# untitled.net
KiCad netlist of a schematic drawn in EAGLE
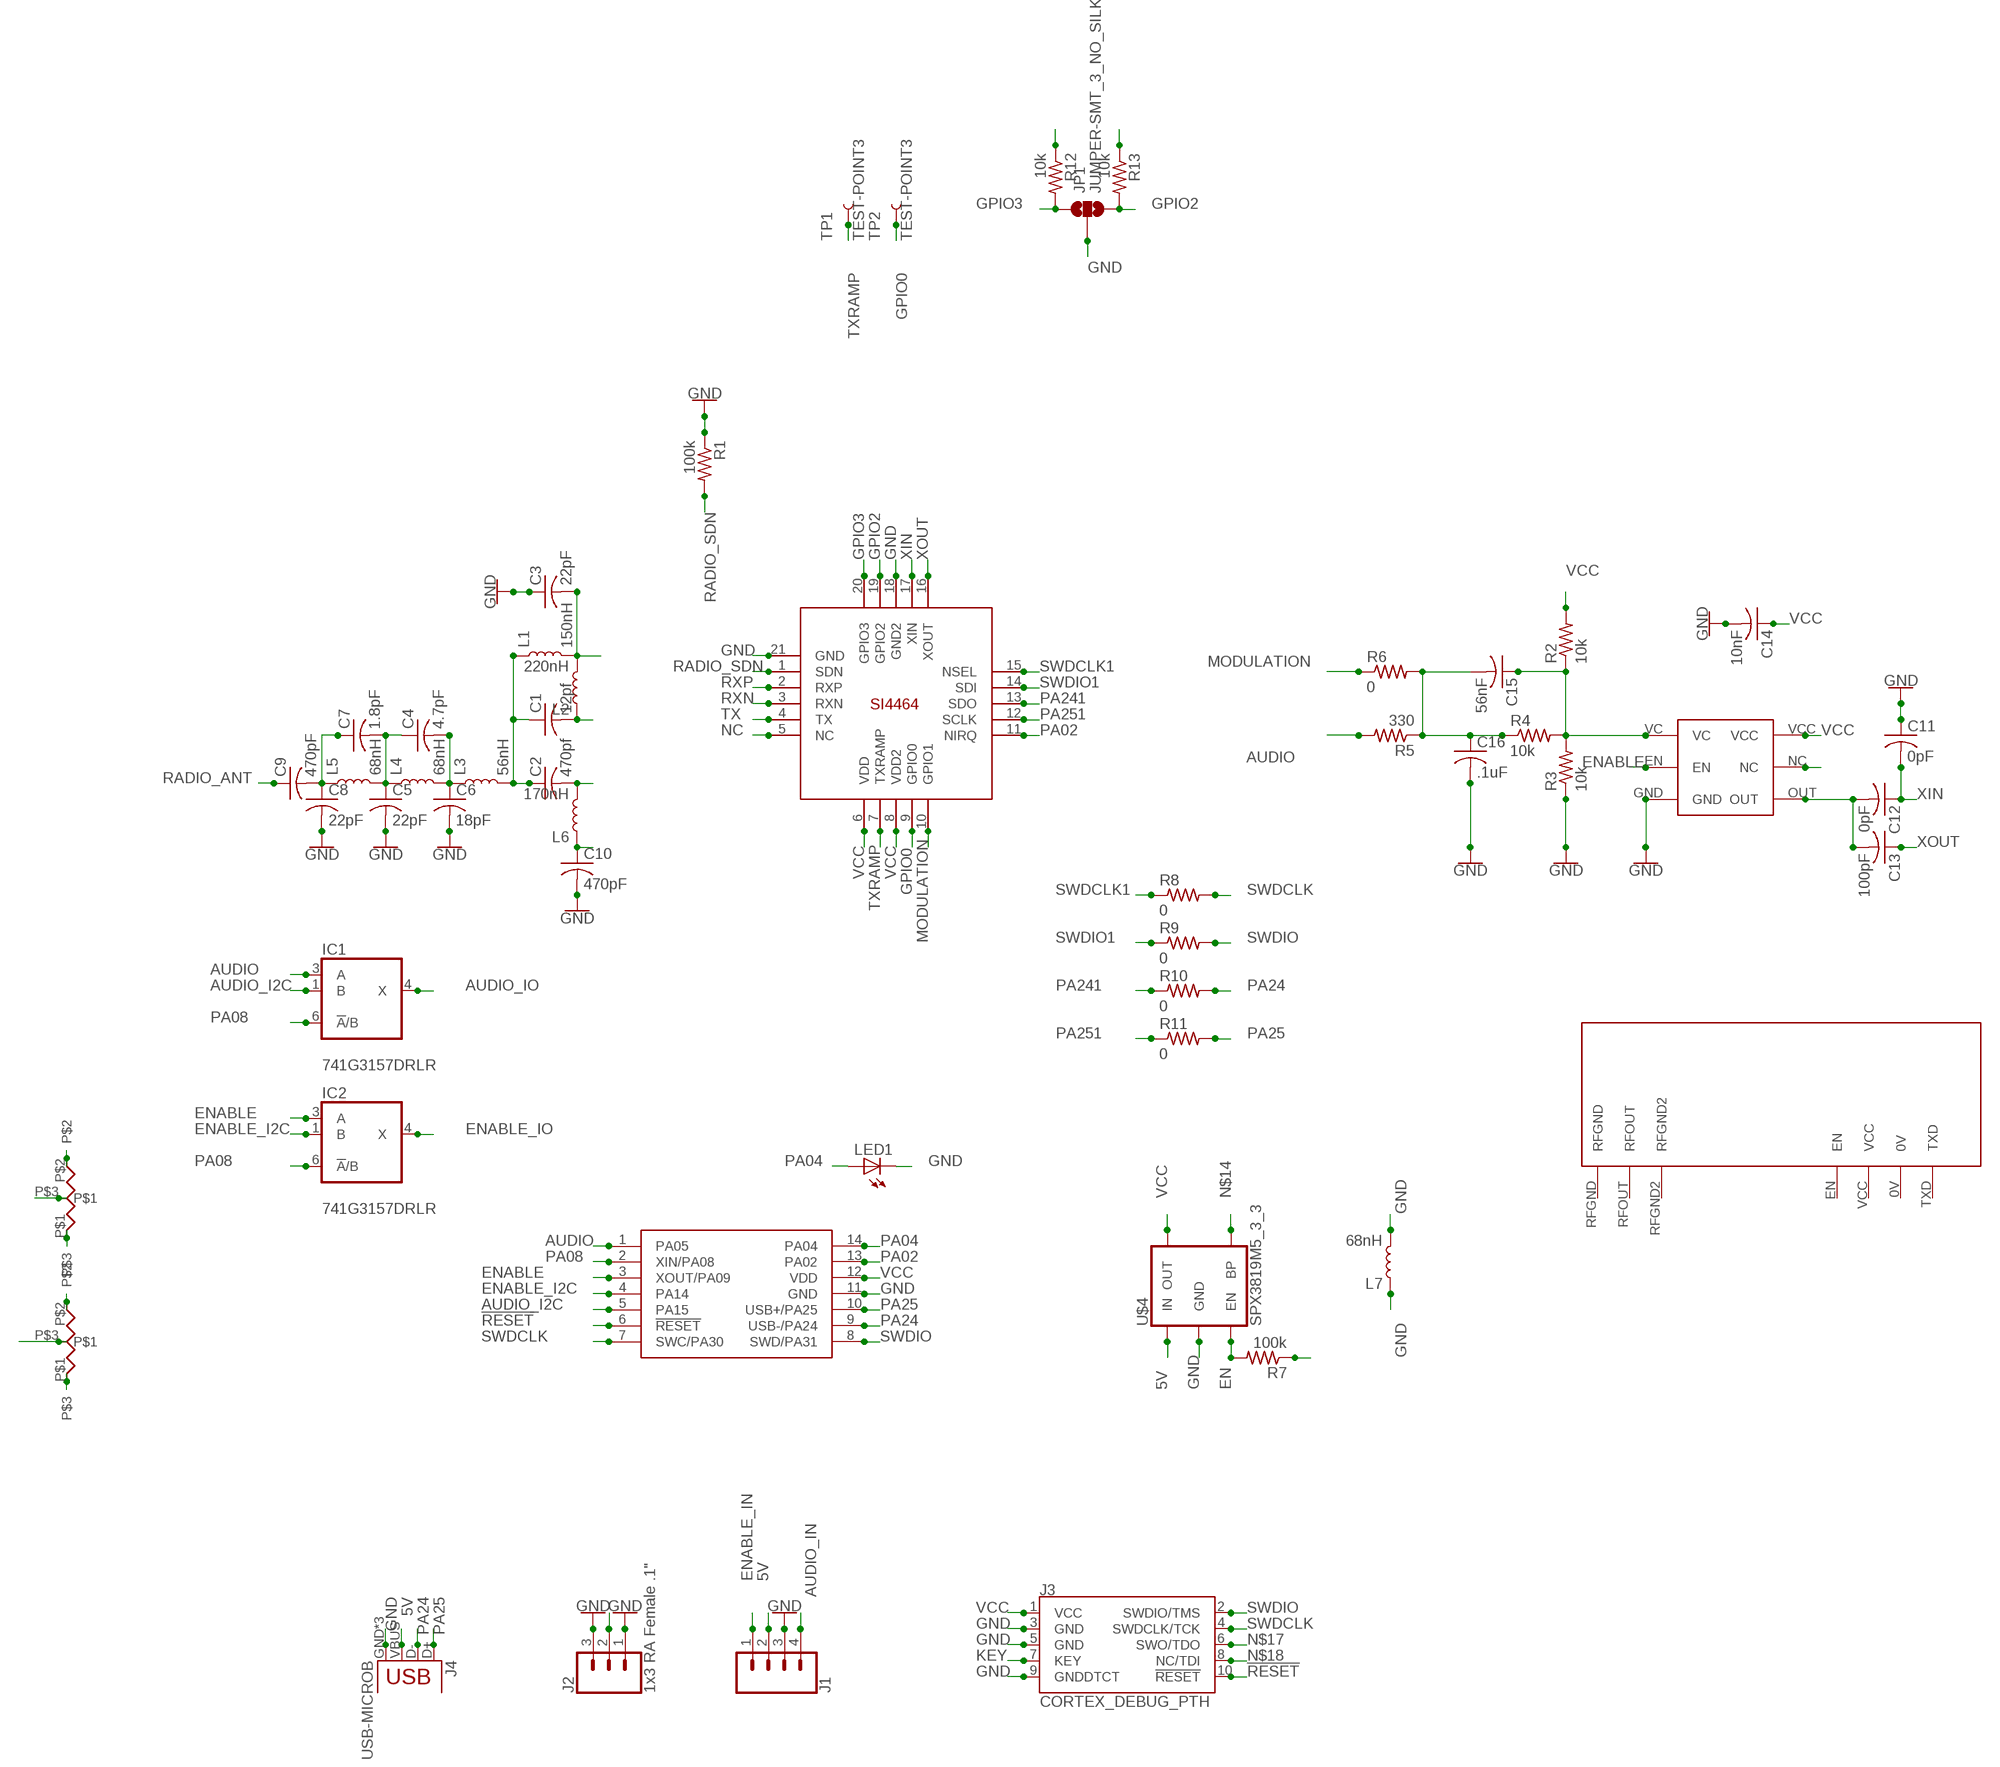
[diagram p0: schematic, sheet 1]

(export (version "E")
  (design (tool "Eeschema 10.0.6"))
  (components
    (comp (ref "C1")
      (value "12pf")
      (footprint "eagle-import:C0402K")
      (libsource (lib "eagle-import") (part "C-USC0402K"))
    )
    (comp (ref "C2")
      (value "470pf")
      (footprint "eagle-import:C0402K")
      (libsource (lib "eagle-import") (part "C-USC0402K"))
    )
    (comp (ref "C3")
      (value "22pF")
      (footprint "eagle-import:C0402K")
      (libsource (lib "eagle-import") (part "C-USC0402K"))
    )
    (comp (ref "C4")
      (value "4.7pF")
      (footprint "eagle-import:C0402K")
      (libsource (lib "eagle-import") (part "C-USC0402K"))
    )
    (comp (ref "C5")
      (value "22pF")
      (footprint "eagle-import:C0402K")
      (libsource (lib "eagle-import") (part "C-USC0402K"))
    )
    (comp (ref "C6")
      (value "18pF")
      (footprint "eagle-import:C0402K")
      (libsource (lib "eagle-import") (part "C-USC0402K"))
    )
    (comp (ref "C7")
      (value "1.8pF")
      (footprint "eagle-import:C0402K")
      (libsource (lib "eagle-import") (part "C-USC0402K"))
    )
    (comp (ref "C8")
      (value "22pF")
      (footprint "eagle-import:C0402K")
      (libsource (lib "eagle-import") (part "C-USC0402K"))
    )
    (comp (ref "C9")
      (value "470pF")
      (footprint "eagle-import:C0402K")
      (libsource (lib "eagle-import") (part "C-USC0402K"))
    )
    (comp (ref "C10")
      (value "470pF")
      (footprint "eagle-import:C0402K")
      (libsource (lib "eagle-import") (part "C-USC0402K"))
    )
    (comp (ref "C11")
      (value "0pF")
      (footprint "eagle-import:C0402K")
      (libsource (lib "eagle-import") (part "C-USC0402K"))
    )
    (comp (ref "C12")
      (value "0pF")
      (footprint "eagle-import:C0402K")
      (libsource (lib "eagle-import") (part "C-USC0402K"))
    )
    (comp (ref "C13")
      (value "100pF")
      (footprint "eagle-import:C0402K")
      (libsource (lib "eagle-import") (part "C-USC0402K"))
    )
    (comp (ref "C14")
      (value "10nF")
      (footprint "eagle-import:C0402K")
      (libsource (lib "eagle-import") (part "C-USC0402K"))
    )
    (comp (ref "C15")
      (value "56nF")
      (footprint "eagle-import:C0402K")
      (libsource (lib "eagle-import") (part "C-USC0402K"))
    )
    (comp (ref "C16")
      (value ".1uF")
      (footprint "eagle-import:C0402K")
      (libsource (lib "eagle-import") (part "C-USC0402K"))
    )
    (comp (ref "IC1")
      (value "741G3157DRLR")
      (footprint "eagle-import:DRL_R-PDSO-N6")
      (libsource (lib "eagle-import") (part "741G3157DRLR"))
    )
    (comp (ref "IC2")
      (value "741G3157DRLR")
      (footprint "eagle-import:DRL_R-PDSO-N6")
      (libsource (lib "eagle-import") (part "741G3157DRLR"))
    )
    (comp (ref "J1")
      (value "CONN_04SMD_RA_FEMALE")
      (footprint "eagle-import:1X04_SMD_RA_FEMALE")
      (libsource (lib "eagle-import") (part "CONN_04SMD_RA_FEMALE"))
    )
    (comp (ref "J2")
      (value "1x3 RA Female .1\"")
      (footprint "eagle-import:1X03_SMD_RA_FEMALE")
      (libsource (lib "eagle-import") (part "CONN_03SMD_RA_FEMALE"))
    )
    (comp (ref "J3")
      (value "CORTEX_DEBUG_PTH")
      (footprint "eagle-import:2X5-PTH-1.27MM")
      (libsource (lib "eagle-import") (part "CORTEX_DEBUG_PTH"))
    )
    (comp (ref "J4")
      (value "USB-MICROB")
      (footprint "eagle-import:USB-MICROB")
      (libsource (lib "eagle-import") (part "USB-MICROB"))
    )
    (comp (ref "JP1")
      (value "JUMPER-SMT_3_NO_SILK")
      (footprint "eagle-import:SMT-JUMPER_3_NO_SILK")
      (libsource (lib "eagle-import") (part "JUMPER-SMT_3_NO_SILK"))
    )
    (comp (ref "L1")
      (value "150nH")
      (footprint "eagle-import:0603")
      (libsource (lib "eagle-import") (part "INDUCTOR-0603-33NH"))
    )
    (comp (ref "L2")
      (value "220nH")
      (footprint "eagle-import:0603")
      (libsource (lib "eagle-import") (part "INDUCTOR-0603-33NH"))
    )
    (comp (ref "L3")
      (value "56nH")
      (footprint "eagle-import:0603")
      (libsource (lib "eagle-import") (part "INDUCTOR-0603-33NH"))
    )
    (comp (ref "L4")
      (value "68nH")
      (footprint "eagle-import:0603")
      (libsource (lib "eagle-import") (part "INDUCTOR-0603-33NH"))
    )
    (comp (ref "L5")
      (value "68nH")
      (footprint "eagle-import:0603")
      (libsource (lib "eagle-import") (part "INDUCTOR-0603-33NH"))
    )
    (comp (ref "L6")
      (value "170nH")
      (footprint "eagle-import:0603")
      (libsource (lib "eagle-import") (part "INDUCTOR-0603-33NH"))
    )
    (comp (ref "L7")
      (value "68nH")
      (footprint "eagle-import:0603")
      (libsource (lib "eagle-import") (part "INDUCTOR-0603-33NH"))
    )
    (comp (ref "LED1")
      (value "LEDCHIP-LED0603")
      (footprint "eagle-import:CHIP-LED0603")
      (libsource (lib "eagle-import") (part "LEDCHIP-LED0603"))
    )
    (comp (ref "R1")
      (value "100k")
      (footprint "eagle-import:R0402")
      (libsource (lib "eagle-import") (part "R-US_R0402"))
    )
    (comp (ref "R2")
      (value "10k")
      (footprint "eagle-import:R0402")
      (libsource (lib "eagle-import") (part "R-US_R0402"))
    )
    (comp (ref "R3")
      (value "10k")
      (footprint "eagle-import:R0402")
      (libsource (lib "eagle-import") (part "R-US_R0402"))
    )
    (comp (ref "R4")
      (value "10k")
      (footprint "eagle-import:R0402")
      (libsource (lib "eagle-import") (part "R-US_R0402"))
    )
    (comp (ref "R5")
      (value "330")
      (footprint "eagle-import:R0402")
      (libsource (lib "eagle-import") (part "R-US_R0402"))
    )
    (comp (ref "R6")
      (value "0")
      (footprint "eagle-import:R0402")
      (libsource (lib "eagle-import") (part "R-US_R0402"))
    )
    (comp (ref "R7")
      (value "100k")
      (footprint "eagle-import:R0402")
      (libsource (lib "eagle-import") (part "R-US_R0402"))
    )
    (comp (ref "R8")
      (value "0")
      (footprint "eagle-import:R0402")
      (libsource (lib "eagle-import") (part "R-US_R0402"))
    )
    (comp (ref "R9")
      (value "0")
      (footprint "eagle-import:R0402")
      (libsource (lib "eagle-import") (part "R-US_R0402"))
    )
    (comp (ref "R10")
      (value "0")
      (footprint "eagle-import:R0402")
      (libsource (lib "eagle-import") (part "R-US_R0402"))
    )
    (comp (ref "R11")
      (value "0")
      (footprint "eagle-import:R0402")
      (libsource (lib "eagle-import") (part "R-US_R0402"))
    )
    (comp (ref "R12")
      (value "10k")
      (footprint "eagle-import:R0402")
      (libsource (lib "eagle-import") (part "R-US_R0402"))
    )
    (comp (ref "R13")
      (value "10k")
      (footprint "eagle-import:R0402")
      (libsource (lib "eagle-import") (part "R-US_R0402"))
    )
    (comp (ref "TP1")
      (value "TEST-POINT3")
      (footprint "eagle-import:PAD.03X.03")
      (libsource (lib "eagle-import") (part "TEST-POINT3"))
    )
    (comp (ref "TP2")
      (value "TEST-POINT3")
      (footprint "eagle-import:PAD.03X.03")
      (libsource (lib "eagle-import") (part "TEST-POINT3"))
    )
    (comp (ref "U$1")
      (value "HC53BR-27")
      (footprint "eagle-import:OSCILLATOR-SMD-7.5X5.2-6PIN")
      (libsource (lib "eagle-import") (part "HC53BR-27"))
    )
    (comp (ref "U$2")
      (value "SI4464")
      (footprint "eagle-import:QFN20+GNDPAD")
      (libsource (lib "eagle-import") (part "SI4464"))
    )
    (comp (ref "U$3")
      (value "SAMD11C14")
      (footprint "eagle-import:SOIC14")
      (libsource (lib "eagle-import") (part "SAMD11C14"))
    )
    (comp (ref "U$4")
      (value "SPX3819M5_3_3")
      (footprint "eagle-import:SOT23-5")
      (libsource (lib "eagle-import") (part "V_REG_SPX3819-SOT23-5"))
    )
    (comp (ref "U$5")
      (value "RM20A10K/20K")
      (footprint "eagle-import:RM20A10K_20K")
      (libsource (lib "eagle-import") (part "RM20A10K/20K"))
    )
    (comp (ref "U$6")
      (value "RM20A10K/20K")
      (footprint "eagle-import:RM20A10K_20K")
      (libsource (lib "eagle-import") (part "RM20A10K/20K"))
    )
    (comp (ref "U$7")
      (value "RADIOMETRIX-HX1")
      (footprint "eagle-import:RADIOMETRIX-HX1")
      (libsource (lib "eagle-import") (part "RADIOMETRIX-HX1"))
    )
  )
  (nets
    (net (code "1") (name "/5V") (class "Default")
      (node (ref "J1") (pin "2") (pinfunction "2_2") (pintype "passive"))
      (node (ref "J4") (pin "VBUS") (pinfunction "VBUS_VBUS") (pintype "bidirectional"))
      (node (ref "R7") (pin "1") (pinfunction "1_1") (pintype "passive"))
      (node (ref "U$4") (pin "1") (pinfunction "IN_1") (pintype "input"))
    )
    (net (code "2") (name "/AUDIO") (class "Default")
      (node (ref "IC1") (pin "3") (pinfunction "A_3") (pintype "bidirectional"))
      (node (ref "R5") (pin "2") (pinfunction "2_2") (pintype "passive"))
      (node (ref "U$3") (pin "1") (pinfunction "PA05_1") (pintype "bidirectional"))
    )
    (net (code "3") (name "/AUDIO_I2C") (class "Default")
      (node (ref "IC1") (pin "1") (pinfunction "B_1") (pintype "bidirectional"))
      (node (ref "U$3") (pin "5") (pinfunction "PA15_5") (pintype "bidirectional"))
    )
    (net (code "4") (name "/AUDIO_IN") (class "Default")
      (node (ref "J1") (pin "4") (pinfunction "4_4") (pintype "passive"))
      (node (ref "U$6") (pin "P$1") (pinfunction "P$3_P$1") (pintype "bidirectional"))
    )
    (net (code "5") (name "/AUDIO_IO") (class "Default")
      (node (ref "IC1") (pin "4") (pinfunction "X_4") (pintype "bidirectional"))
      (node (ref "U$6") (pin "P$3") (pinfunction "P$1_P$3") (pintype "bidirectional"))
    )
    (net (code "6") (name "/EN") (class "Default")
      (node (ref "R7") (pin "2") (pinfunction "2_2") (pintype "passive"))
      (node (ref "U$4") (pin "3") (pinfunction "EN_3") (pintype "input"))
    )
    (net (code "7") (name "/ENABLE") (class "Default")
      (node (ref "IC2") (pin "3") (pinfunction "A_3") (pintype "bidirectional"))
      (node (ref "U$1") (pin "EN") (pinfunction "EN_EN") (pintype "bidirectional"))
      (node (ref "U$3") (pin "3") (pinfunction "XOUT/PA09_3") (pintype "bidirectional"))
    )
    (net (code "8") (name "/ENABLE_I2C") (class "Default")
      (node (ref "IC2") (pin "1") (pinfunction "B_1") (pintype "bidirectional"))
      (node (ref "U$3") (pin "4") (pinfunction "PA14_4") (pintype "bidirectional"))
    )
    (net (code "9") (name "/ENABLE_IN") (class "Default")
      (node (ref "J1") (pin "1") (pinfunction "1_1") (pintype "passive"))
      (node (ref "U$5") (pin "P$1") (pinfunction "P$3_P$1") (pintype "bidirectional"))
    )
    (net (code "10") (name "/ENABLE_IO") (class "Default")
      (node (ref "IC2") (pin "4") (pinfunction "X_4") (pintype "bidirectional"))
      (node (ref "U$5") (pin "P$3") (pinfunction "P$1_P$3") (pintype "bidirectional"))
    )
    (net (code "11") (name "/GPIO0") (class "Default")
      (node (ref "TP2") (pin "P$1") (pinfunction "1_P$1") (pintype "bidirectional"))
      (node (ref "U$2") (pin "9") (pinfunction "GPIO0_9") (pintype "bidirectional"))
    )
    (net (code "12") (name "/GPIO2") (class "Default")
      (node (ref "JP1") (pin "3") (pinfunction "3_3") (pintype "passive"))
      (node (ref "R13") (pin "2") (pinfunction "2_2") (pintype "passive"))
      (node (ref "U$2") (pin "19") (pinfunction "GPIO2_19") (pintype "bidirectional"))
    )
    (net (code "13") (name "/GPIO3") (class "Default")
      (node (ref "JP1") (pin "1") (pinfunction "1_1") (pintype "passive"))
      (node (ref "R12") (pin "2") (pinfunction "2_2") (pintype "passive"))
      (node (ref "U$2") (pin "20") (pinfunction "GPIO3_20") (pintype "bidirectional"))
    )
    (net (code "14") (name "/KEY") (class "Default")
      (node (ref "J3") (pin "7") (pinfunction "KEY_7") (pintype "bidirectional"))
    )
    (net (code "15") (name "/MODULATION") (class "Default")
      (node (ref "R6") (pin "1") (pinfunction "1_1") (pintype "passive"))
      (node (ref "U$2") (pin "10") (pinfunction "GPIO1_10") (pintype "bidirectional"))
    )
    (net (code "16") (name "/N$14") (class "Default")
      (node (ref "U$4") (pin "4") (pinfunction "BP_4") (pintype "input"))
    )
    (net (code "17") (name "/N$17") (class "Default")
      (node (ref "J3") (pin "6") (pinfunction "SWO/TDO_6") (pintype "bidirectional"))
    )
    (net (code "18") (name "/N$18") (class "Default")
      (node (ref "J3") (pin "8") (pinfunction "NC/TDI_8") (pintype "bidirectional"))
    )
    (net (code "19") (name "/NC") (class "Default")
      (node (ref "U$2") (pin "5") (pinfunction "NC _5") (pintype "bidirectional"))
    )
    (net (code "20") (name "/PA02") (class "Default")
      (node (ref "U$2") (pin "11") (pinfunction "NIRQ_11") (pintype "bidirectional"))
      (node (ref "U$3") (pin "13") (pinfunction "PA02_13") (pintype "bidirectional"))
    )
    (net (code "21") (name "/PA04") (class "Default")
      (node (ref "LED1") (pin "A") (pinfunction "A_A") (pintype "passive"))
      (node (ref "U$3") (pin "14") (pinfunction "PA04_14") (pintype "bidirectional"))
    )
    (net (code "22") (name "/PA08") (class "Default")
      (node (ref "IC1") (pin "6") (pinfunction "~{A}/B_6") (pintype "input"))
      (node (ref "IC2") (pin "6") (pinfunction "~{A}/B_6") (pintype "input"))
      (node (ref "U$3") (pin "2") (pinfunction "XIN/PA08_2") (pintype "bidirectional"))
    )
    (net (code "23") (name "/PA24") (class "Default")
      (node (ref "J4") (pin "D-") (pinfunction "D-_D-") (pintype "bidirectional"))
      (node (ref "R10") (pin "2") (pinfunction "2_2") (pintype "passive"))
      (node (ref "U$3") (pin "9") (pinfunction "USB-/PA24_9") (pintype "bidirectional"))
    )
    (net (code "24") (name "/PA25") (class "Default")
      (node (ref "J4") (pin "D+") (pinfunction "D+_D+") (pintype "bidirectional"))
      (node (ref "R11") (pin "2") (pinfunction "2_2") (pintype "passive"))
      (node (ref "U$3") (pin "10") (pinfunction "USB+/PA25_10") (pintype "bidirectional"))
    )
    (net (code "25") (name "/PA241") (class "Default")
      (node (ref "R10") (pin "1") (pinfunction "1_1") (pintype "passive"))
      (node (ref "U$2") (pin "13") (pinfunction "SDO_13") (pintype "bidirectional"))
    )
    (net (code "26") (name "/PA251") (class "Default")
      (node (ref "R11") (pin "1") (pinfunction "1_1") (pintype "passive"))
      (node (ref "U$2") (pin "12") (pinfunction "SCLK_12") (pintype "bidirectional"))
    )
    (net (code "27") (name "/RADIO_ANT") (class "Default")
      (node (ref "C9") (pin "1") (pinfunction "1_1") (pintype "passive"))
      (node (ref "J2") (pin "2") (pinfunction "2_2") (pintype "passive"))
    )
    (net (code "28") (name "/RADIO_SDN") (class "Default")
      (node (ref "R1") (pin "2") (pinfunction "2_2") (pintype "passive"))
      (node (ref "U$2") (pin "1") (pinfunction "SDN_1") (pintype "bidirectional"))
    )
    (net (code "29") (name "/RXN") (class "Default")
      (node (ref "C1") (pin "2") (pinfunction "2_2") (pintype "passive"))
      (node (ref "L2") (pin "1") (pinfunction "1_1") (pintype "passive"))
      (node (ref "U$2") (pin "3") (pinfunction "RXN_3") (pintype "bidirectional"))
    )
    (net (code "30") (name "/RXP") (class "Default")
      (node (ref "C3") (pin "2") (pinfunction "2_2") (pintype "passive"))
      (node (ref "L1") (pin "2") (pinfunction "2_2") (pintype "passive"))
      (node (ref "L2") (pin "2") (pinfunction "2_2") (pintype "passive"))
      (node (ref "U$2") (pin "2") (pinfunction "RXP_2") (pintype "bidirectional"))
    )
    (net (code "31") (name "/SWDCLK") (class "Default")
      (node (ref "J3") (pin "4") (pinfunction "SWDCLK/TCK_4") (pintype "bidirectional"))
      (node (ref "R8") (pin "2") (pinfunction "2_2") (pintype "passive"))
      (node (ref "U$3") (pin "7") (pinfunction "SWC/PA30_7") (pintype "bidirectional"))
    )
    (net (code "32") (name "/SWDCLK1") (class "Default")
      (node (ref "R8") (pin "1") (pinfunction "1_1") (pintype "passive"))
      (node (ref "U$2") (pin "15") (pinfunction "NSEL_15") (pintype "bidirectional"))
    )
    (net (code "33") (name "/SWDIO") (class "Default")
      (node (ref "J3") (pin "2") (pinfunction "SWDIO/TMS_2") (pintype "bidirectional"))
      (node (ref "R9") (pin "2") (pinfunction "2_2") (pintype "passive"))
      (node (ref "U$3") (pin "8") (pinfunction "SWD/PA31_8") (pintype "bidirectional"))
    )
    (net (code "34") (name "/SWDIO1") (class "Default")
      (node (ref "R9") (pin "1") (pinfunction "1_1") (pintype "passive"))
      (node (ref "U$2") (pin "14") (pinfunction "SDI_14") (pintype "bidirectional"))
    )
    (net (code "35") (name "/TX") (class "Default")
      (node (ref "C2") (pin "2") (pinfunction "2_2") (pintype "passive"))
      (node (ref "L6") (pin "2") (pinfunction "2_2") (pintype "passive"))
      (node (ref "U$2") (pin "4") (pinfunction "TX_4") (pintype "bidirectional"))
    )
    (net (code "36") (name "/TXRAMP") (class "Default")
      (node (ref "TP1") (pin "P$1") (pinfunction "1_P$1") (pintype "bidirectional"))
      (node (ref "U$2") (pin "7") (pinfunction "TXRAMP_7") (pintype "bidirectional"))
    )
    (net (code "37") (name "/VCC") (class "Default")
      (node (ref "C10") (pin "1") (pinfunction "1_1") (pintype "passive"))
      (node (ref "C14") (pin "1") (pinfunction "1_1") (pintype "passive"))
      (node (ref "J3") (pin "1") (pinfunction "VCC_1") (pintype "bidirectional"))
      (node (ref "L6") (pin "1") (pinfunction "1_1") (pintype "passive"))
      (node (ref "R12") (pin "1") (pinfunction "1_1") (pintype "passive"))
      (node (ref "R13") (pin "1") (pinfunction "1_1") (pintype "passive"))
      (node (ref "R2") (pin "2") (pinfunction "2_2") (pintype "passive"))
      (node (ref "U$1") (pin "VCC") (pinfunction "VCC_VCC") (pintype "bidirectional"))
      (node (ref "U$2") (pin "6") (pinfunction "VDD_6") (pintype "bidirectional"))
      (node (ref "U$2") (pin "8") (pinfunction "VDD2_8") (pintype "bidirectional"))
      (node (ref "U$3") (pin "12") (pinfunction "VDD_12") (pintype "bidirectional"))
      (node (ref "U$4") (pin "5") (pinfunction "OUT_5") (pintype "passive"))
    )
    (net (code "38") (name "/XIN") (class "Default")
      (node (ref "C11") (pin "2") (pinfunction "2_2") (pintype "passive"))
      (node (ref "C12") (pin "1") (pinfunction "1_1") (pintype "passive"))
      (node (ref "U$2") (pin "17") (pinfunction "XIN_17") (pintype "bidirectional"))
    )
    (net (code "39") (name "/XOUT") (class "Default")
      (node (ref "C13") (pin "1") (pinfunction "1_1") (pintype "passive"))
      (node (ref "U$2") (pin "16") (pinfunction "XOUT_16") (pintype "bidirectional"))
    )
    (net (code "40") (name "/~{RESET}") (class "Default")
      (node (ref "J3") (pin "10") (pinfunction "~{RESET}_10") (pintype "bidirectional"))
      (node (ref "U$3") (pin "6") (pinfunction "~{RESET}_6") (pintype "bidirectional"))
    )
    (net (code "41") (name "GND") (class "Default")
      (node (ref "C10") (pin "2") (pinfunction "2_2") (pintype "passive"))
      (node (ref "C11") (pin "1") (pinfunction "1_1") (pintype "passive"))
      (node (ref "C14") (pin "2") (pinfunction "2_2") (pintype "passive"))
      (node (ref "C16") (pin "2") (pinfunction "2_2") (pintype "passive"))
      (node (ref "C3") (pin "1") (pinfunction "1_1") (pintype "passive"))
      (node (ref "C5") (pin "2") (pinfunction "2_2") (pintype "passive"))
      (node (ref "C6") (pin "2") (pinfunction "2_2") (pintype "passive"))
      (node (ref "C8") (pin "2") (pinfunction "2_2") (pintype "passive"))
      (node (ref "J1") (pin "3") (pinfunction "3_3") (pintype "passive"))
      (node (ref "J2") (pin "1") (pinfunction "1_1") (pintype "passive"))
      (node (ref "J2") (pin "3") (pinfunction "3_3") (pintype "passive"))
      (node (ref "J3") (pin "3") (pinfunction "GND_3") (pintype "bidirectional"))
      (node (ref "J3") (pin "5") (pinfunction "GND_5") (pintype "bidirectional"))
      (node (ref "J3") (pin "9") (pinfunction "GNDDTCT_9") (pintype "bidirectional"))
      (node (ref "J4") (pin "GND") (pinfunction "GND_GND") (pintype "bidirectional"))
      (node (ref "J4") (pin "MT1") (pinfunction "GND_MT1") (pintype "bidirectional"))
      (node (ref "J4") (pin "MT2") (pinfunction "GND_MT2") (pintype "bidirectional"))
      (node (ref "JP1") (pin "2") (pinfunction "2_2") (pintype "passive"))
      (node (ref "L7") (pin "1") (pinfunction "1_1") (pintype "passive"))
      (node (ref "L7") (pin "2") (pinfunction "2_2") (pintype "passive"))
      (node (ref "LED1") (pin "C") (pinfunction "C_C") (pintype "passive"))
      (node (ref "R1") (pin "1") (pinfunction "1_1") (pintype "passive"))
      (node (ref "R3") (pin "1") (pinfunction "1_1") (pintype "passive"))
      (node (ref "U$1") (pin "GND") (pinfunction "GND_GND") (pintype "bidirectional"))
      (node (ref "U$2") (pin "18") (pinfunction "GND2_18") (pintype "bidirectional"))
      (node (ref "U$2") (pin "21") (pinfunction "GND_21") (pintype "bidirectional"))
      (node (ref "U$3") (pin "11") (pinfunction "GND_11") (pintype "bidirectional"))
      (node (ref "U$4") (pin "2") (pinfunction "GND_2") (pintype "input"))
      (node (ref "U$5") (pin "P$2") (pinfunction "P$2_P$2") (pintype "bidirectional"))
      (node (ref "U$6") (pin "P$2") (pinfunction "P$2_P$2") (pintype "bidirectional"))
    )
    (net (code "42") (name "Net-(C1-Pad1)") (class "Default")
      (node (ref "C1") (pin "1") (pinfunction "1_1") (pintype "passive"))
      (node (ref "C2") (pin "1") (pinfunction "1_1") (pintype "passive"))
      (node (ref "L1") (pin "1") (pinfunction "1_1") (pintype "passive"))
      (node (ref "L3") (pin "2") (pinfunction "2_2") (pintype "passive"))
    )
    (net (code "43") (name "Net-(C4-Pad1)") (class "Default")
      (node (ref "C4") (pin "1") (pinfunction "1_1") (pintype "passive"))
      (node (ref "C5") (pin "1") (pinfunction "1_1") (pintype "passive"))
      (node (ref "C7") (pin "2") (pinfunction "2_2") (pintype "passive"))
      (node (ref "L4") (pin "1") (pinfunction "1_1") (pintype "passive"))
      (node (ref "L5") (pin "2") (pinfunction "2_2") (pintype "passive"))
    )
    (net (code "44") (name "Net-(C4-Pad2)") (class "Default")
      (node (ref "C4") (pin "2") (pinfunction "2_2") (pintype "passive"))
      (node (ref "C6") (pin "1") (pinfunction "1_1") (pintype "passive"))
      (node (ref "L3") (pin "1") (pinfunction "1_1") (pintype "passive"))
      (node (ref "L4") (pin "2") (pinfunction "2_2") (pintype "passive"))
    )
    (net (code "45") (name "Net-(C7-Pad1)") (class "Default")
      (node (ref "C7") (pin "1") (pinfunction "1_1") (pintype "passive"))
      (node (ref "C8") (pin "1") (pinfunction "1_1") (pintype "passive"))
      (node (ref "C9") (pin "2") (pinfunction "2_2") (pintype "passive"))
      (node (ref "L5") (pin "1") (pinfunction "1_1") (pintype "passive"))
    )
    (net (code "46") (name "Net-(C12-Pad2)") (class "Default")
      (node (ref "C12") (pin "2") (pinfunction "2_2") (pintype "passive"))
      (node (ref "C13") (pin "2") (pinfunction "2_2") (pintype "passive"))
      (node (ref "U$1") (pin "OUT") (pinfunction "OUT_OUT") (pintype "bidirectional"))
    )
    (net (code "47") (name "Net-(C15-Pad1)") (class "Default")
      (node (ref "C15") (pin "1") (pinfunction "1_1") (pintype "passive"))
      (node (ref "R2") (pin "1") (pinfunction "1_1") (pintype "passive"))
      (node (ref "R3") (pin "2") (pinfunction "2_2") (pintype "passive"))
      (node (ref "R4") (pin "2") (pinfunction "2_2") (pintype "passive"))
      (node (ref "U$1") (pin "VC") (pinfunction "VC_VC") (pintype "bidirectional"))
    )
    (net (code "48") (name "Net-(C15-Pad2)") (class "Default")
      (node (ref "C15") (pin "2") (pinfunction "2_2") (pintype "passive"))
      (node (ref "C16") (pin "1") (pinfunction "1_1") (pintype "passive"))
      (node (ref "R4") (pin "1") (pinfunction "1_1") (pintype "passive"))
      (node (ref "R5") (pin "1") (pinfunction "1_1") (pintype "passive"))
      (node (ref "R6") (pin "2") (pinfunction "2_2") (pintype "passive"))
    )
    (net (code "49") (name "unconnected-(U$1-PadNC)") (class "Default")
      (node (ref "U$1") (pin "NC") (pinfunction "NC_NC") (pintype "bidirectional"))
    )
    (net (code "50") (name "unconnected-(U$7-Pad0V)") (class "Default")
      (node (ref "U$7") (pin "0V") (pinfunction "0V_0V") (pintype "bidirectional"))
    )
    (net (code "51") (name "unconnected-(U$7-PadEN)") (class "Default")
      (node (ref "U$7") (pin "EN") (pinfunction "EN_EN") (pintype "bidirectional"))
    )
    (net (code "52") (name "unconnected-(U$7-PadRFGND)") (class "Default")
      (node (ref "U$7") (pin "RFGND") (pinfunction "RFGND_RFGND") (pintype "bidirectional"))
    )
    (net (code "53") (name "unconnected-(U$7-PadRFGND2)") (class "Default")
      (node (ref "U$7") (pin "RFGND2") (pinfunction "RFGND2_RFGND2") (pintype "bidirectional"))
    )
    (net (code "54") (name "unconnected-(U$7-PadRFOUT)") (class "Default")
      (node (ref "U$7") (pin "RFOUT") (pinfunction "RFOUT_RFOUT") (pintype "bidirectional"))
    )
    (net (code "55") (name "unconnected-(U$7-PadTXD)") (class "Default")
      (node (ref "U$7") (pin "TXD") (pinfunction "TXD_TXD") (pintype "bidirectional"))
    )
    (net (code "56") (name "unconnected-(U$7-PadVCC)") (class "Default")
      (node (ref "U$7") (pin "VCC") (pinfunction "VCC_VCC") (pintype "bidirectional"))
    )
  )
)
